# StatusBot-1.net
KiCad netlist of a schematic drawn in EAGLE
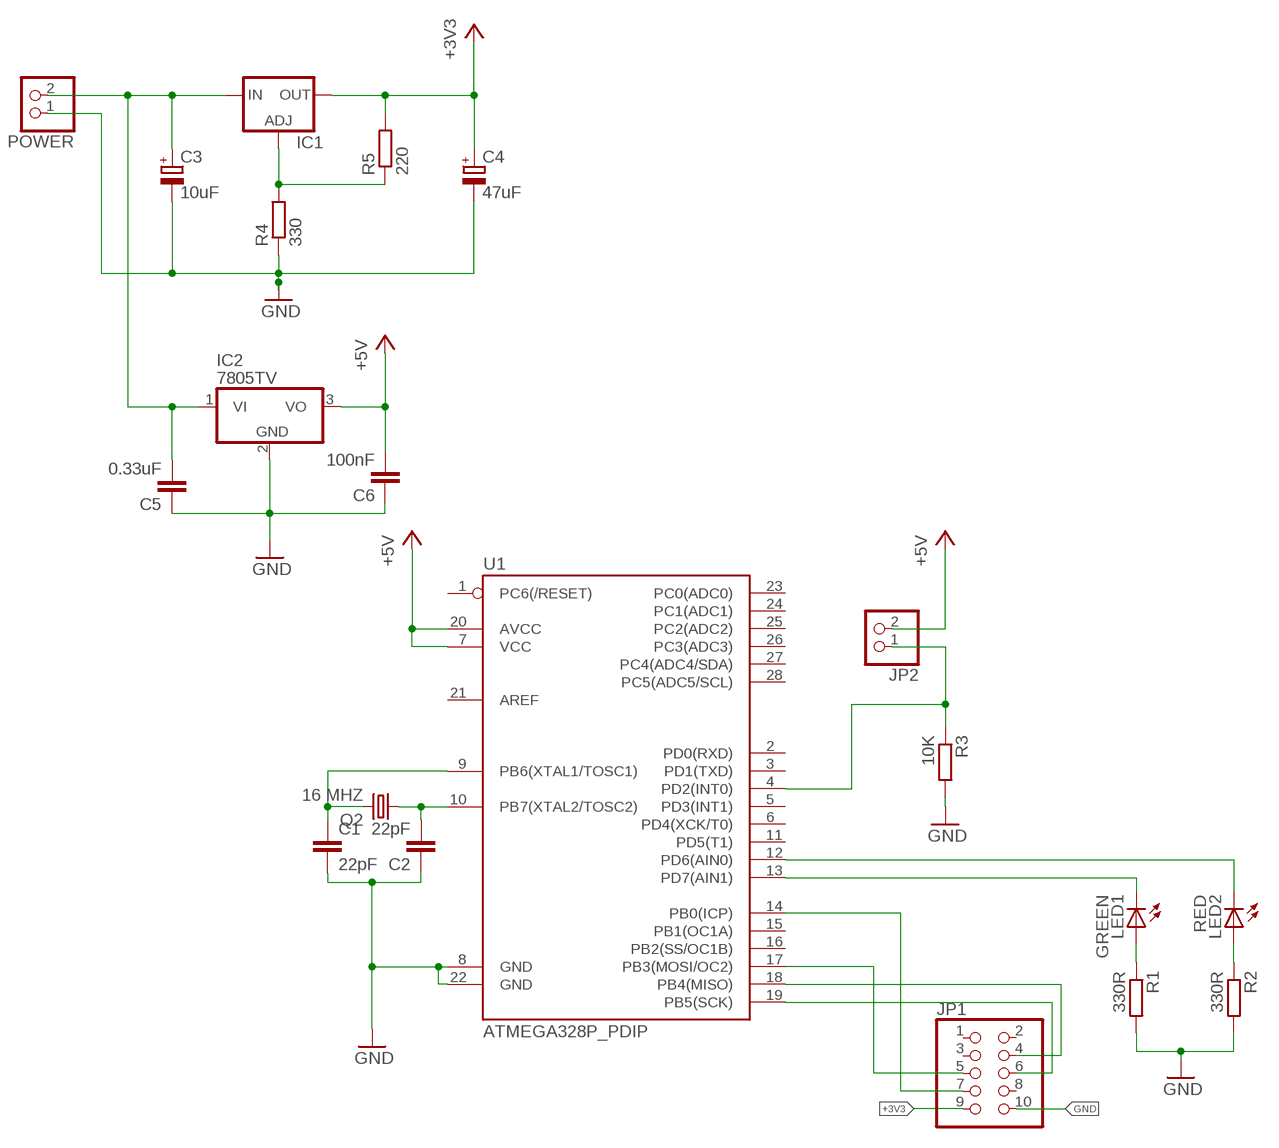
[diagram p0: schematic, sheet 1]

(export (version "E")
  (design (tool "Eeschema 10.0.6"))
  (components
    (comp (ref "C1")
      (value "22pF")
      (footprint "eagle-import:C025-024X044")
      (libsource (lib "eagle-import") (part "C-EU025-024X044"))
    )
    (comp (ref "C2")
      (value "22pF")
      (footprint "eagle-import:C025-024X044")
      (libsource (lib "eagle-import") (part "C-EU025-024X044"))
    )
    (comp (ref "C3")
      (value "10uF")
      (footprint "eagle-import:E3,5-8")
      (libsource (lib "eagle-import") (part "CPOL-EUE3.5-8"))
    )
    (comp (ref "C4")
      (value "47uF")
      (footprint "eagle-import:E3,5-8")
      (libsource (lib "eagle-import") (part "CPOL-EUE3.5-8"))
    )
    (comp (ref "C5")
      (value "0.33uF")
      (footprint "eagle-import:C025-024X044")
      (libsource (lib "eagle-import") (part "C-EU025-024X044"))
    )
    (comp (ref "C6")
      (value "100nF")
      (footprint "eagle-import:C025-024X044")
      (libsource (lib "eagle-import") (part "C-EU025-024X044"))
    )
    (comp (ref "IC1")
      (value "LM317TS")
      (footprint "eagle-import:317TS")
      (libsource (lib "eagle-import") (part "LM317TS"))
    )
    (comp (ref "IC2")
      (value "7805TV")
      (footprint "eagle-import:TO220V")
      (libsource (lib "eagle-import") (part "78TV05"))
    )
    (comp (ref "JP1")
      (value "PINHD-2X5")
      (footprint "eagle-import:2X05")
      (libsource (lib "eagle-import") (part "PINHD-2X5"))
    )
    (comp (ref "JP2")
      (value "PINHD-1X2")
      (footprint "eagle-import:1X02")
      (libsource (lib "eagle-import") (part "PINHD-1X2"))
    )
    (comp (ref "LED1")
      (value "GREEN")
      (footprint "eagle-import:LED5MM")
      (libsource (lib "eagle-import") (part "LED5MM"))
    )
    (comp (ref "LED2")
      (value "RED")
      (footprint "eagle-import:LED5MM")
      (libsource (lib "eagle-import") (part "LED5MM"))
    )
    (comp (ref "POWER")
      (value "PINHD-1X2")
      (footprint "eagle-import:1X02")
      (libsource (lib "eagle-import") (part "PINHD-1X2"))
    )
    (comp (ref "Q2")
      (value "16 MHZ")
      (footprint "eagle-import:HC49_S")
      (libsource (lib "eagle-import") (part "CRYSTALHC49S"))
    )
    (comp (ref "R1")
      (value "330R")
      (footprint "eagle-import:0204_5")
      (libsource (lib "eagle-import") (part "R-EU_0204/5"))
    )
    (comp (ref "R2")
      (value "330R")
      (footprint "eagle-import:0204_5")
      (libsource (lib "eagle-import") (part "R-EU_0204/5"))
    )
    (comp (ref "R3")
      (value "10K")
      (footprint "eagle-import:0204_5")
      (libsource (lib "eagle-import") (part "R-EU_0204/5"))
    )
    (comp (ref "R4")
      (value "330")
      (footprint "eagle-import:0207_10")
      (libsource (lib "eagle-import") (part "resistor_R-EU_0207/10"))
    )
    (comp (ref "R5")
      (value "220")
      (footprint "eagle-import:0207_10")
      (libsource (lib "eagle-import") (part "resistor_R-EU_0207/10"))
    )
    (comp (ref "U1")
      (value "ATMEGA328P_PDIP")
      (footprint "eagle-import:DIL28-3")
      (libsource (lib "eagle-import") (part "ATMEGA328P_PDIP"))
    )
  )
  (nets
    (net (code "1") (name "+3V3") (class "Default")
      (node (ref "C4") (pin "+") (pinfunction "+_+") (pintype "passive"))
      (node (ref "IC1") (pin "2") (pinfunction "OUT_2") (pintype "passive"))
      (node (ref "JP1") (pin "9") (pinfunction "9_9") (pintype "passive"))
      (node (ref "R5") (pin "2") (pinfunction "2_2") (pintype "passive"))
    )
    (net (code "2") (name "+5V") (class "Default")
      (node (ref "C6") (pin "2") (pinfunction "2_2") (pintype "passive"))
      (node (ref "IC2") (pin "3") (pinfunction "VO_3") (pintype "passive"))
      (node (ref "JP2") (pin "2") (pinfunction "2_2") (pintype "passive"))
      (node (ref "U1") (pin "20") (pinfunction "AVCC_20") (pintype "bidirectional"))
      (node (ref "U1") (pin "7") (pinfunction "VCC_7") (pintype "bidirectional"))
    )
    (net (code "3") (name "GND") (class "Default")
      (node (ref "C1") (pin "2") (pinfunction "2_2") (pintype "passive"))
      (node (ref "C2") (pin "1") (pinfunction "1_1") (pintype "passive"))
      (node (ref "C3") (pin "-") (pinfunction "-_-") (pintype "passive"))
      (node (ref "C4") (pin "-") (pinfunction "-_-") (pintype "passive"))
      (node (ref "C5") (pin "1") (pinfunction "1_1") (pintype "passive"))
      (node (ref "C6") (pin "1") (pinfunction "1_1") (pintype "passive"))
      (node (ref "IC2") (pin "2") (pinfunction "GND_2") (pintype "passive"))
      (node (ref "JP1") (pin "10") (pinfunction "10_10") (pintype "passive"))
      (node (ref "POWER") (pin "1") (pinfunction "1_1") (pintype "passive"))
      (node (ref "R1") (pin "2") (pinfunction "2_2") (pintype "passive"))
      (node (ref "R2") (pin "2") (pinfunction "2_2") (pintype "passive"))
      (node (ref "R3") (pin "2") (pinfunction "2_2") (pintype "passive"))
      (node (ref "R4") (pin "1") (pinfunction "1_1") (pintype "passive"))
      (node (ref "U1") (pin "22") (pinfunction "GND_22") (pintype "bidirectional"))
      (node (ref "U1") (pin "8") (pinfunction "GND_8") (pintype "bidirectional"))
    )
    (net (code "4") (name "Net-(IC1-ADJ)") (class "Default")
      (node (ref "IC1") (pin "1") (pinfunction "ADJ_1") (pintype "input"))
      (node (ref "R4") (pin "2") (pinfunction "2_2") (pintype "passive"))
      (node (ref "R5") (pin "1") (pinfunction "1_1") (pintype "passive"))
    )
    (net (code "5") (name "Net-(IC1-IN)") (class "Default")
      (node (ref "C3") (pin "+") (pinfunction "+_+") (pintype "passive"))
      (node (ref "C5") (pin "2") (pinfunction "2_2") (pintype "passive"))
      (node (ref "IC1") (pin "3") (pinfunction "IN_3") (pintype "input"))
      (node (ref "IC2") (pin "1") (pinfunction "VI_1") (pintype "input"))
      (node (ref "POWER") (pin "2") (pinfunction "2_2") (pintype "passive"))
    )
    (net (code "6") (name "Net-(LED1-C)") (class "Default")
      (node (ref "LED1") (pin "K") (pinfunction "C_K") (pintype "passive"))
      (node (ref "U1") (pin "13") (pinfunction "PD7(AIN1)_13") (pintype "bidirectional"))
    )
    (net (code "7") (name "Net-(LED1-PadA)") (class "Default")
      (node (ref "LED1") (pin "A") (pinfunction "A_A") (pintype "passive"))
      (node (ref "R1") (pin "1") (pinfunction "1_1") (pintype "passive"))
    )
    (net (code "8") (name "Net-(LED2-C)") (class "Default")
      (node (ref "LED2") (pin "K") (pinfunction "C_K") (pintype "passive"))
      (node (ref "U1") (pin "12") (pinfunction "PD6(AIN0)_12") (pintype "bidirectional"))
    )
    (net (code "9") (name "Net-(LED2-PadA)") (class "Default")
      (node (ref "LED2") (pin "A") (pinfunction "A_A") (pintype "passive"))
      (node (ref "R2") (pin "1") (pinfunction "1_1") (pintype "passive"))
    )
    (net (code "10") (name "Net-(U1-PB0(ICP))") (class "Default")
      (node (ref "JP1") (pin "7") (pinfunction "7_7") (pintype "passive"))
      (node (ref "U1") (pin "14") (pinfunction "PB0(ICP)_14") (pintype "bidirectional"))
    )
    (net (code "11") (name "Net-(U1-PB3(MOSI{slash}OC2))") (class "Default")
      (node (ref "JP1") (pin "5") (pinfunction "5_5") (pintype "passive"))
      (node (ref "U1") (pin "17") (pinfunction "PB3(MOSI/OC2)_17") (pintype "bidirectional"))
    )
    (net (code "12") (name "Net-(U1-PB4(MISO))") (class "Default")
      (node (ref "JP1") (pin "4") (pinfunction "4_4") (pintype "passive"))
      (node (ref "U1") (pin "18") (pinfunction "PB4(MISO)_18") (pintype "bidirectional"))
    )
    (net (code "13") (name "Net-(U1-PB5(SCK))") (class "Default")
      (node (ref "JP1") (pin "6") (pinfunction "6_6") (pintype "passive"))
      (node (ref "U1") (pin "19") (pinfunction "PB5(SCK)_19") (pintype "bidirectional"))
    )
    (net (code "14") (name "Net-(U1-PB6(XTAL1{slash}TOSC1))") (class "Default")
      (node (ref "C1") (pin "1") (pinfunction "1_1") (pintype "passive"))
      (node (ref "Q2") (pin "2") (pinfunction "2_2") (pintype "passive"))
      (node (ref "U1") (pin "9") (pinfunction "PB6(XTAL1/TOSC1)_9") (pintype "bidirectional"))
    )
    (net (code "15") (name "Net-(U1-PB7(XTAL2{slash}TOSC2))") (class "Default")
      (node (ref "C2") (pin "2") (pinfunction "2_2") (pintype "passive"))
      (node (ref "Q2") (pin "1") (pinfunction "1_1") (pintype "passive"))
      (node (ref "U1") (pin "10") (pinfunction "PB7(XTAL2/TOSC2)_10") (pintype "bidirectional"))
    )
    (net (code "16") (name "Net-(U1-PD2(INT0))") (class "Default")
      (node (ref "JP2") (pin "1") (pinfunction "1_1") (pintype "passive"))
      (node (ref "R3") (pin "1") (pinfunction "1_1") (pintype "passive"))
      (node (ref "U1") (pin "4") (pinfunction "PD2(INT0)_4") (pintype "bidirectional"))
    )
    (net (code "17") (name "unconnected-(JP1-Pad1)") (class "Default")
      (node (ref "JP1") (pin "1") (pinfunction "1_1") (pintype "passive"))
    )
    (net (code "18") (name "unconnected-(JP1-Pad2)") (class "Default")
      (node (ref "JP1") (pin "2") (pinfunction "2_2") (pintype "passive"))
    )
    (net (code "19") (name "unconnected-(JP1-Pad3)") (class "Default")
      (node (ref "JP1") (pin "3") (pinfunction "3_3") (pintype "passive"))
    )
    (net (code "20") (name "unconnected-(JP1-Pad8)") (class "Default")
      (node (ref "JP1") (pin "8") (pinfunction "8_8") (pintype "passive"))
    )
    (net (code "21") (name "unconnected-(U1-AREF-Pad21)") (class "Default")
      (node (ref "U1") (pin "21") (pinfunction "AREF_21") (pintype "bidirectional"))
    )
    (net (code "22") (name "unconnected-(U1-PB1(OC1A)-Pad15)") (class "Default")
      (node (ref "U1") (pin "15") (pinfunction "PB1(OC1A)_15") (pintype "bidirectional"))
    )
    (net (code "23") (name "unconnected-(U1-PB2(SS{slash}OC1B)-Pad16)") (class "Default")
      (node (ref "U1") (pin "16") (pinfunction "PB2(SS/OC1B)_16") (pintype "bidirectional"))
    )
    (net (code "24") (name "unconnected-(U1-PC0(ADC0)-Pad23)") (class "Default")
      (node (ref "U1") (pin "23") (pinfunction "PC0(ADC0)_23") (pintype "bidirectional"))
    )
    (net (code "25") (name "unconnected-(U1-PC1(ADC1)-Pad24)") (class "Default")
      (node (ref "U1") (pin "24") (pinfunction "PC1(ADC1)_24") (pintype "bidirectional"))
    )
    (net (code "26") (name "unconnected-(U1-PC2(ADC2)-Pad25)") (class "Default")
      (node (ref "U1") (pin "25") (pinfunction "PC2(ADC2)_25") (pintype "bidirectional"))
    )
    (net (code "27") (name "unconnected-(U1-PC3(ADC3)-Pad26)") (class "Default")
      (node (ref "U1") (pin "26") (pinfunction "PC3(ADC3)_26") (pintype "bidirectional"))
    )
    (net (code "28") (name "unconnected-(U1-PC4(ADC4{slash}SDA)-Pad27)") (class "Default")
      (node (ref "U1") (pin "27") (pinfunction "PC4(ADC4/SDA)_27") (pintype "bidirectional"))
    )
    (net (code "29") (name "unconnected-(U1-PC5(ADC5{slash}SCL)-Pad28)") (class "Default")
      (node (ref "U1") (pin "28") (pinfunction "PC5(ADC5/SCL)_28") (pintype "bidirectional"))
    )
    (net (code "30") (name "unconnected-(U1-PC6({slash}RESET)-Pad1)") (class "Default")
      (node (ref "U1") (pin "1") (pinfunction "PC6(/RESET)_1") (pintype "bidirectional"))
    )
    (net (code "31") (name "unconnected-(U1-PD0(RXD)-Pad2)") (class "Default")
      (node (ref "U1") (pin "2") (pinfunction "PD0(RXD)_2") (pintype "bidirectional"))
    )
    (net (code "32") (name "unconnected-(U1-PD1(TXD)-Pad3)") (class "Default")
      (node (ref "U1") (pin "3") (pinfunction "PD1(TXD)_3") (pintype "bidirectional"))
    )
    (net (code "33") (name "unconnected-(U1-PD3(INT1)-Pad5)") (class "Default")
      (node (ref "U1") (pin "5") (pinfunction "PD3(INT1)_5") (pintype "bidirectional"))
    )
    (net (code "34") (name "unconnected-(U1-PD4(XCK{slash}T0)-Pad6)") (class "Default")
      (node (ref "U1") (pin "6") (pinfunction "PD4(XCK/T0)_6") (pintype "bidirectional"))
    )
    (net (code "35") (name "unconnected-(U1-PD5(T1)-Pad11)") (class "Default")
      (node (ref "U1") (pin "11") (pinfunction "PD5(T1)_11") (pintype "bidirectional"))
    )
  )
)
